# BlueToothStepperV2.net
KiCad netlist of a schematic drawn in EAGLE
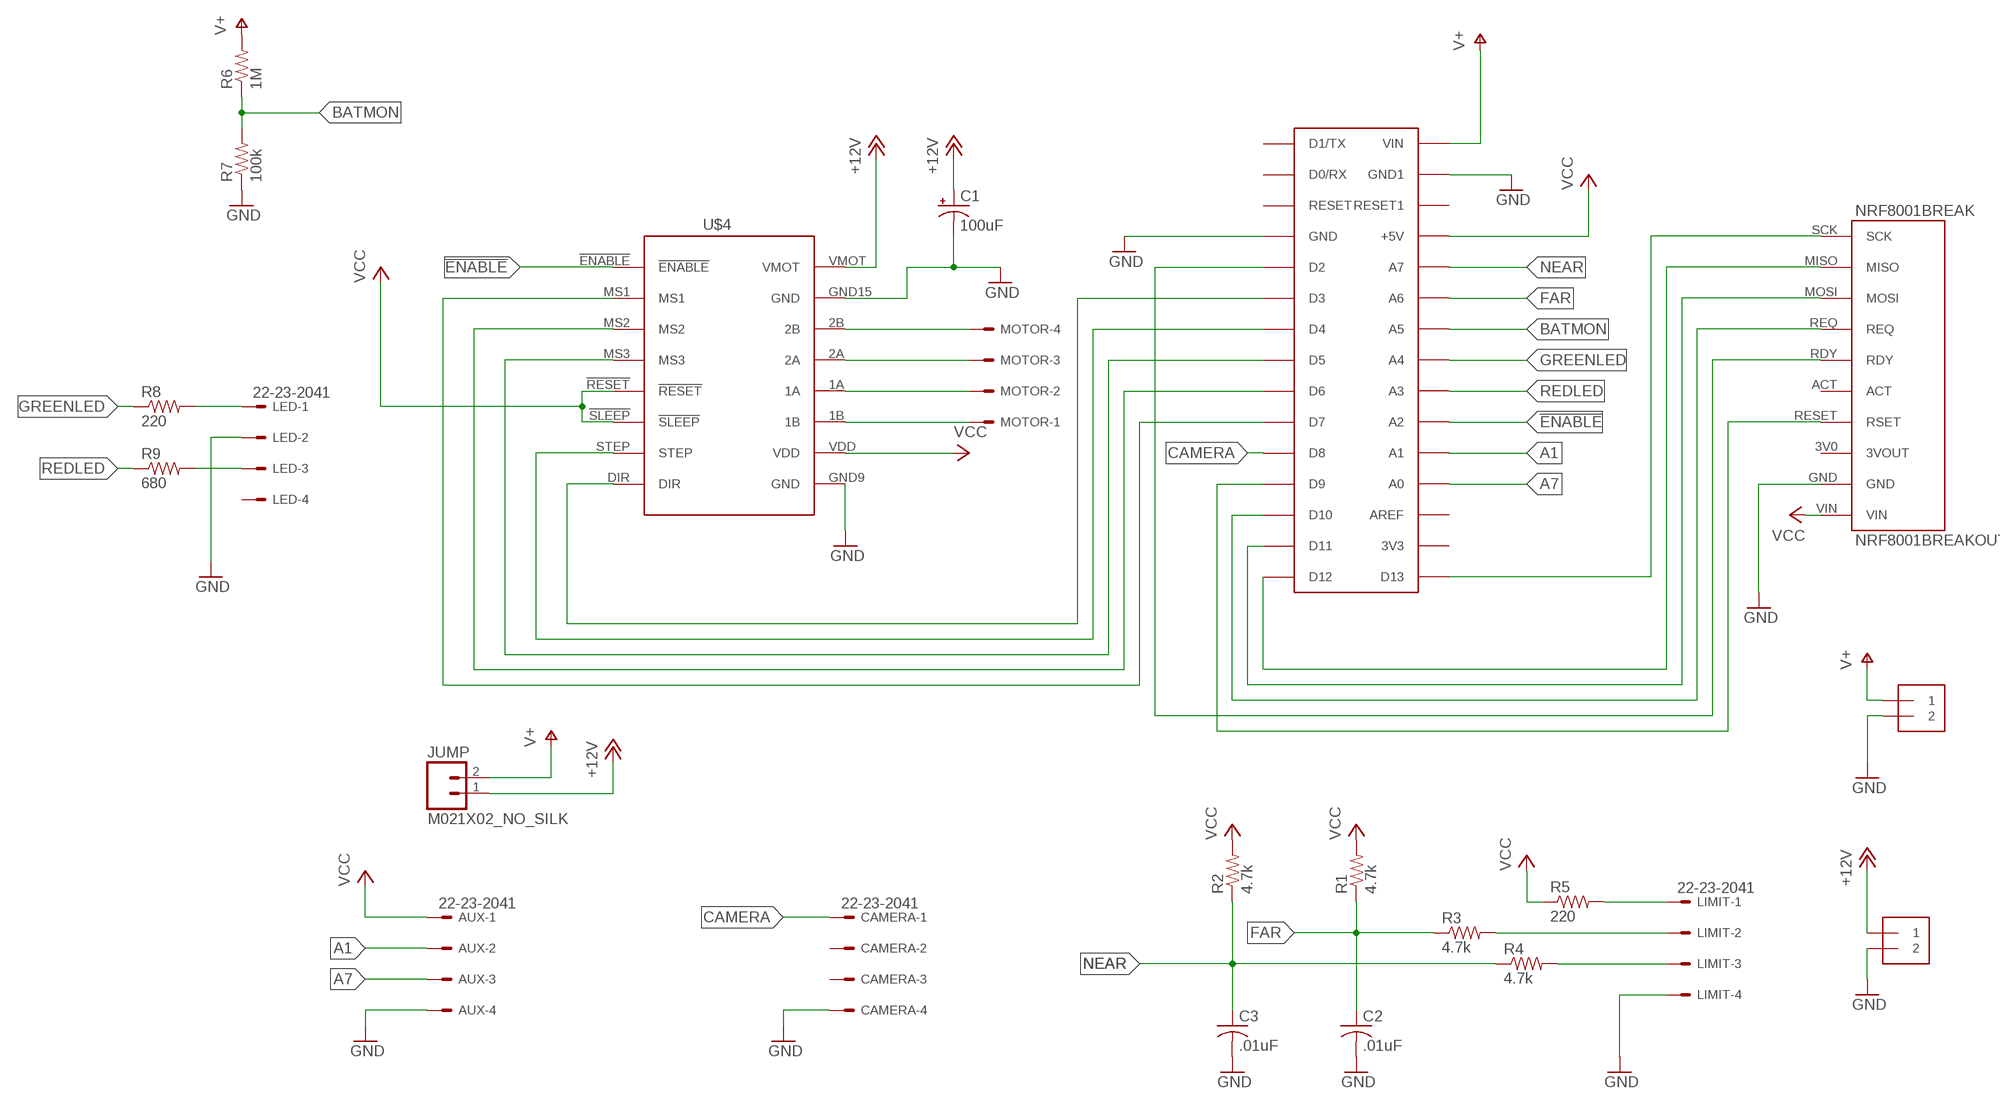
[diagram p0: schematic, sheet 1]

(export (version "E")
  (design (tool "Eeschema 10.0.6"))
  (components
    (comp (ref "7VOLT")
      (value "1X2-3.5MM")
      (footprint "eagle-import:1X2-3.5MM")
      (libsource (lib "eagle-import") (part "1X2-3.5MM"))
    )
    (comp (ref "12VOLT")
      (value "1X2-3.5MM")
      (footprint "eagle-import:1X2-3.5MM")
      (libsource (lib "eagle-import") (part "1X2-3.5MM"))
    )
    (comp (ref "AUX")
      (value "22-23-2041")
      (footprint "eagle-import:22-23-2041")
      (fields (field (name "MF") "MOLEX"))
      (libsource (lib "eagle-import") (part "22-23-2041"))
    )
    (comp (ref "C1")
      (value "100uF")
      (footprint "eagle-import:E3,5-8")
      (libsource (lib "eagle-import") (part "CPOL-USE3.5-8"))
    )
    (comp (ref "C2")
      (value ".01uF")
      (footprint "eagle-import:C050-030X075")
      (libsource (lib "eagle-import") (part "C-US050-030X075"))
    )
    (comp (ref "C3")
      (value ".01uF")
      (footprint "eagle-import:C050-030X075")
      (libsource (lib "eagle-import") (part "C-US050-030X075"))
    )
    (comp (ref "CAMERA")
      (value "22-23-2041")
      (footprint "eagle-import:22-23-2041")
      (fields (field (name "MF") "MOLEX"))
      (libsource (lib "eagle-import") (part "22-23-2041"))
    )
    (comp (ref "JUMP")
      (value "M021X02_NO_SILK")
      (footprint "eagle-import:1X02_NO_SILK")
      (libsource (lib "eagle-import") (part "M021X02_NO_SILK"))
    )
    (comp (ref "LED")
      (value "22-23-2041")
      (footprint "eagle-import:22-23-2041")
      (fields (field (name "MF") "MOLEX"))
      (libsource (lib "eagle-import") (part "22-23-2041"))
    )
    (comp (ref "LIMIT")
      (value "22-23-2041")
      (footprint "eagle-import:22-23-2041")
      (fields (field (name "MF") "MOLEX"))
      (libsource (lib "eagle-import") (part "22-23-2041"))
    )
    (comp (ref "MOTOR")
      (value "22-23-2041")
      (footprint "eagle-import:22-23-2041")
      (fields (field (name "MF") "MOLEX"))
      (libsource (lib "eagle-import") (part "22-23-2041"))
    )
    (comp (ref "NANO")
      (value "ARDUINONANO")
      (footprint "eagle-import:PDIP-32")
      (libsource (lib "eagle-import") (part "ARDUINONANO"))
    )
    (comp (ref "NRF8001BREAK")
      (value "NRF8001BREAKOUT")
      (footprint "eagle-import:BREAKOUTV2")
      (libsource (lib "eagle-import") (part "NRF8001BREAKOUT"))
    )
    (comp (ref "R1")
      (value "4.7k")
      (footprint "eagle-import:0207_9")
      (libsource (lib "eagle-import") (part "R-US_0207/9"))
    )
    (comp (ref "R2")
      (value "4.7k")
      (footprint "eagle-import:0207_9")
      (libsource (lib "eagle-import") (part "R-US_0207/9"))
    )
    (comp (ref "R3")
      (value "4.7k")
      (footprint "eagle-import:0207_9")
      (libsource (lib "eagle-import") (part "R-US_0207/9"))
    )
    (comp (ref "R4")
      (value "4.7k")
      (footprint "eagle-import:0207_9")
      (libsource (lib "eagle-import") (part "R-US_0207/9"))
    )
    (comp (ref "R5")
      (value "220")
      (footprint "eagle-import:0207_9")
      (libsource (lib "eagle-import") (part "R-US_0207/9"))
    )
    (comp (ref "R6")
      (value "1M")
      (footprint "eagle-import:0207_9")
      (libsource (lib "eagle-import") (part "R-US_0207/9"))
    )
    (comp (ref "R7")
      (value "100k")
      (footprint "eagle-import:0207_9")
      (libsource (lib "eagle-import") (part "R-US_0207/9"))
    )
    (comp (ref "R8")
      (value "220")
      (footprint "eagle-import:0207_9")
      (libsource (lib "eagle-import") (part "R-US_0207/9"))
    )
    (comp (ref "R9")
      (value "680")
      (footprint "eagle-import:0207_9")
      (libsource (lib "eagle-import") (part "R-US_0207/9"))
    )
    (comp (ref "U$4")
      (value "STEPPER1616PINV2")
      (footprint "eagle-import:STEPPER16PINV2")
      (libsource (lib "eagle-import") (part "STEPPER1616PINV2"))
    )
  )
  (nets
    (net (code "1") (name "+12V") (class "Default")
      (node (ref "12VOLT") (pin "1") (pinfunction "1_1") (pintype "passive"))
      (node (ref "C1") (pin "+") (pinfunction "+_+") (pintype "passive"))
      (node (ref "JUMP") (pin "1") (pinfunction "1_1") (pintype "passive"))
      (node (ref "U$4") (pin "VMOT") (pinfunction "VMOT_VMOT") (pintype "bidirectional"))
    )
    (net (code "2") (name "/~{ENABLE}") (class "Default")
      (node (ref "NANO") (pin "A2") (pinfunction "A2_A2") (pintype "bidirectional"))
      (node (ref "U$4") (pin "!ENABLE") (pinfunction "~{ENABLE}_!ENABLE") (pintype "bidirectional"))
    )
    (net (code "3") (name "A1") (class "Default")
      (node (ref "AUX") (pin "2") (pinfunction "S_2") (pintype "passive"))
      (node (ref "NANO") (pin "A1") (pinfunction "A1_A1") (pintype "bidirectional"))
    )
    (net (code "4") (name "A7") (class "Default")
      (node (ref "AUX") (pin "3") (pinfunction "S_3") (pintype "passive"))
      (node (ref "NANO") (pin "A0") (pinfunction "A0_A0") (pintype "bidirectional"))
    )
    (net (code "5") (name "BATMON") (class "Default")
      (node (ref "NANO") (pin "A5") (pinfunction "A5_A5") (pintype "bidirectional"))
      (node (ref "R6") (pin "1") (pinfunction "1_1") (pintype "passive"))
      (node (ref "R7") (pin "2") (pinfunction "2_2") (pintype "passive"))
    )
    (net (code "6") (name "CAMERA") (class "Default")
      (node (ref "CAMERA") (pin "1") (pinfunction "S_1") (pintype "passive"))
      (node (ref "NANO") (pin "D8") (pinfunction "D8_D8") (pintype "bidirectional"))
    )
    (net (code "7") (name "FAR") (class "Default")
      (node (ref "C2") (pin "1") (pinfunction "1_1") (pintype "passive"))
      (node (ref "NANO") (pin "A6") (pinfunction "A6_A6") (pintype "bidirectional"))
      (node (ref "R1") (pin "1") (pinfunction "1_1") (pintype "passive"))
      (node (ref "R3") (pin "1") (pinfunction "1_1") (pintype "passive"))
    )
    (net (code "8") (name "GND") (class "Default")
      (node (ref "12VOLT") (pin "2") (pinfunction "2_2") (pintype "passive"))
      (node (ref "7VOLT") (pin "2") (pinfunction "2_2") (pintype "passive"))
      (node (ref "AUX") (pin "4") (pinfunction "S_4") (pintype "passive"))
      (node (ref "C1") (pin "-") (pinfunction "-_-") (pintype "passive"))
      (node (ref "C2") (pin "2") (pinfunction "2_2") (pintype "passive"))
      (node (ref "C3") (pin "2") (pinfunction "2_2") (pintype "passive"))
      (node (ref "CAMERA") (pin "4") (pinfunction "S_4") (pintype "passive"))
      (node (ref "LED") (pin "2") (pinfunction "S_2") (pintype "passive"))
      (node (ref "LIMIT") (pin "4") (pinfunction "S_4") (pintype "passive"))
      (node (ref "NANO") (pin "GND") (pinfunction "GND_GND") (pintype "bidirectional"))
      (node (ref "NANO") (pin "GND1") (pinfunction "GND1_GND1") (pintype "bidirectional"))
      (node (ref "NRF8001BREAK") (pin "GND") (pinfunction "GND_GND") (pintype "bidirectional"))
      (node (ref "R7") (pin "1") (pinfunction "1_1") (pintype "passive"))
      (node (ref "U$4") (pin "GND15") (pinfunction "GND_GND15") (pintype "bidirectional"))
      (node (ref "U$4") (pin "GND9") (pinfunction "GND_GND9") (pintype "bidirectional"))
    )
    (net (code "9") (name "GREENLED") (class "Default")
      (node (ref "NANO") (pin "A4") (pinfunction "A4_A4") (pintype "bidirectional"))
      (node (ref "R8") (pin "1") (pinfunction "1_1") (pintype "passive"))
    )
    (net (code "10") (name "NEAR") (class "Default")
      (node (ref "C3") (pin "1") (pinfunction "1_1") (pintype "passive"))
      (node (ref "NANO") (pin "A7") (pinfunction "A7_A7") (pintype "bidirectional"))
      (node (ref "R2") (pin "1") (pinfunction "1_1") (pintype "passive"))
      (node (ref "R4") (pin "1") (pinfunction "1_1") (pintype "passive"))
    )
    (net (code "11") (name "Net-(LEDA-S)") (class "Default")
      (node (ref "LED") (pin "1") (pinfunction "S_1") (pintype "passive"))
      (node (ref "R8") (pin "2") (pinfunction "2_2") (pintype "passive"))
    )
    (net (code "12") (name "Net-(LEDC-S)") (class "Default")
      (node (ref "LED") (pin "3") (pinfunction "S_3") (pintype "passive"))
      (node (ref "R9") (pin "2") (pinfunction "2_2") (pintype "passive"))
    )
    (net (code "13") (name "Net-(LIMITA-S)") (class "Default")
      (node (ref "LIMIT") (pin "1") (pinfunction "S_1") (pintype "passive"))
      (node (ref "R5") (pin "2") (pinfunction "2_2") (pintype "passive"))
    )
    (net (code "14") (name "Net-(LIMITB-S)") (class "Default")
      (node (ref "LIMIT") (pin "2") (pinfunction "S_2") (pintype "passive"))
      (node (ref "R3") (pin "2") (pinfunction "2_2") (pintype "passive"))
    )
    (net (code "15") (name "Net-(LIMITC-S)") (class "Default")
      (node (ref "LIMIT") (pin "3") (pinfunction "S_3") (pintype "passive"))
      (node (ref "R4") (pin "2") (pinfunction "2_2") (pintype "passive"))
    )
    (net (code "16") (name "Net-(MOTORA-S)") (class "Default")
      (node (ref "MOTOR") (pin "1") (pinfunction "S_1") (pintype "passive"))
      (node (ref "U$4") (pin "1B") (pinfunction "1B_1B") (pintype "bidirectional"))
    )
    (net (code "17") (name "Net-(MOTORB-S)") (class "Default")
      (node (ref "MOTOR") (pin "2") (pinfunction "S_2") (pintype "passive"))
      (node (ref "U$4") (pin "1A") (pinfunction "1A_1A") (pintype "bidirectional"))
    )
    (net (code "18") (name "Net-(MOTORC-S)") (class "Default")
      (node (ref "MOTOR") (pin "3") (pinfunction "S_3") (pintype "passive"))
      (node (ref "U$4") (pin "2A") (pinfunction "2A_2A") (pintype "bidirectional"))
    )
    (net (code "19") (name "Net-(MOTORD-S)") (class "Default")
      (node (ref "MOTOR") (pin "4") (pinfunction "S_4") (pintype "passive"))
      (node (ref "U$4") (pin "2B") (pinfunction "2B_2B") (pintype "bidirectional"))
    )
    (net (code "20") (name "Net-(NANO-PadD2)") (class "Default")
      (node (ref "NANO") (pin "D2") (pinfunction "D2_D2") (pintype "bidirectional"))
      (node (ref "NRF8001BREAK") (pin "RDY") (pinfunction "RDY_RDY") (pintype "bidirectional"))
    )
    (net (code "21") (name "Net-(NANO-PadD3)") (class "Default")
      (node (ref "NANO") (pin "D3") (pinfunction "D3_D3") (pintype "bidirectional"))
      (node (ref "U$4") (pin "DIR") (pinfunction "DIR_DIR") (pintype "bidirectional"))
    )
    (net (code "22") (name "Net-(NANO-PadD4)") (class "Default")
      (node (ref "NANO") (pin "D4") (pinfunction "D4_D4") (pintype "bidirectional"))
      (node (ref "U$4") (pin "STEP") (pinfunction "STEP_STEP") (pintype "bidirectional"))
    )
    (net (code "23") (name "Net-(NANO-PadD5)") (class "Default")
      (node (ref "NANO") (pin "D5") (pinfunction "D5_D5") (pintype "bidirectional"))
      (node (ref "U$4") (pin "MS3") (pinfunction "MS3_MS3") (pintype "bidirectional"))
    )
    (net (code "24") (name "Net-(NANO-PadD6)") (class "Default")
      (node (ref "NANO") (pin "D6") (pinfunction "D6_D6") (pintype "bidirectional"))
      (node (ref "U$4") (pin "MS2") (pinfunction "MS2_MS2") (pintype "bidirectional"))
    )
    (net (code "25") (name "Net-(NANO-PadD7)") (class "Default")
      (node (ref "NANO") (pin "D7") (pinfunction "D7_D7") (pintype "bidirectional"))
      (node (ref "U$4") (pin "MS1") (pinfunction "MS1_MS1") (pintype "bidirectional"))
    )
    (net (code "26") (name "Net-(NANO-PadD10)") (class "Default")
      (node (ref "NANO") (pin "D10") (pinfunction "D10_D10") (pintype "bidirectional"))
      (node (ref "NRF8001BREAK") (pin "REQ") (pinfunction "REQ_REQ") (pintype "bidirectional"))
    )
    (net (code "27") (name "Net-(NANO-PadD11)") (class "Default")
      (node (ref "NANO") (pin "D11") (pinfunction "D11_D11") (pintype "bidirectional"))
      (node (ref "NRF8001BREAK") (pin "MOSI") (pinfunction "MOSI_MOSI") (pintype "bidirectional"))
    )
    (net (code "28") (name "Net-(NANO-PadD12)") (class "Default")
      (node (ref "NANO") (pin "D12") (pinfunction "D12_D12") (pintype "bidirectional"))
      (node (ref "NRF8001BREAK") (pin "MISO") (pinfunction "MISO_MISO") (pintype "bidirectional"))
    )
    (net (code "29") (name "Net-(NANO-PadD13)") (class "Default")
      (node (ref "NANO") (pin "D13") (pinfunction "D13_D13") (pintype "bidirectional"))
      (node (ref "NRF8001BREAK") (pin "SCK") (pinfunction "SCK_SCK") (pintype "bidirectional"))
    )
    (net (code "30") (name "Net-(NRF8001BREAK-RSET)") (class "Default")
      (node (ref "NANO") (pin "D9") (pinfunction "D9_D9") (pintype "bidirectional"))
      (node (ref "NRF8001BREAK") (pin "RESET") (pinfunction "RSET_RESET") (pintype "bidirectional"))
    )
    (net (code "31") (name "REDLED") (class "Default")
      (node (ref "NANO") (pin "A3") (pinfunction "A3_A3") (pintype "bidirectional"))
      (node (ref "R9") (pin "1") (pinfunction "1_1") (pintype "passive"))
    )
    (net (code "32") (name "V+") (class "Default")
      (node (ref "7VOLT") (pin "1") (pinfunction "1_1") (pintype "passive"))
      (node (ref "JUMP") (pin "2") (pinfunction "2_2") (pintype "passive"))
      (node (ref "NANO") (pin "VIN") (pinfunction "VIN_VIN") (pintype "bidirectional"))
      (node (ref "R6") (pin "2") (pinfunction "2_2") (pintype "passive"))
    )
    (net (code "33") (name "VCC") (class "Default")
      (node (ref "AUX") (pin "1") (pinfunction "S_1") (pintype "passive"))
      (node (ref "NANO") (pin "+5V") (pinfunction "+5V_+5V") (pintype "bidirectional"))
      (node (ref "NRF8001BREAK") (pin "VIN") (pinfunction "VIN_VIN") (pintype "bidirectional"))
      (node (ref "R1") (pin "2") (pinfunction "2_2") (pintype "passive"))
      (node (ref "R2") (pin "2") (pinfunction "2_2") (pintype "passive"))
      (node (ref "R5") (pin "1") (pinfunction "1_1") (pintype "passive"))
      (node (ref "U$4") (pin "!RESET") (pinfunction "~{RESET}_!RESET") (pintype "bidirectional"))
      (node (ref "U$4") (pin "!SLEEP") (pinfunction "~{SLEEP}_!SLEEP") (pintype "bidirectional"))
      (node (ref "U$4") (pin "VDD") (pinfunction "VDD_VDD") (pintype "bidirectional"))
    )
    (net (code "34") (name "unconnected-(CAMERAB-S-Pad2)") (class "Default")
      (node (ref "CAMERA") (pin "2") (pinfunction "S_2") (pintype "passive"))
    )
    (net (code "35") (name "unconnected-(CAMERAC-S-Pad3)") (class "Default")
      (node (ref "CAMERA") (pin "3") (pinfunction "S_3") (pintype "passive"))
    )
    (net (code "36") (name "unconnected-(LEDD-S-Pad4)") (class "Default")
      (node (ref "LED") (pin "4") (pinfunction "S_4") (pintype "passive"))
    )
    (net (code "37") (name "unconnected-(NANO-Pad3V3)") (class "Default")
      (node (ref "NANO") (pin "3V3") (pinfunction "3V3_3V3") (pintype "bidirectional"))
    )
    (net (code "38") (name "unconnected-(NANO-PadAREF)") (class "Default")
      (node (ref "NANO") (pin "AREF") (pinfunction "AREF_AREF") (pintype "bidirectional"))
    )
    (net (code "39") (name "unconnected-(NANO-PadD0{slash}RX)") (class "Default")
      (node (ref "NANO") (pin "D0/RX") (pinfunction "D0/RX_D0/RX") (pintype "bidirectional"))
    )
    (net (code "40") (name "unconnected-(NANO-PadD1{slash}TX)") (class "Default")
      (node (ref "NANO") (pin "D1/TX") (pinfunction "D1/TX_D1/TX") (pintype "bidirectional"))
    )
    (net (code "41") (name "unconnected-(NANO-PadRESET)") (class "Default")
      (node (ref "NANO") (pin "RESET") (pinfunction "RESET_RESET") (pintype "bidirectional"))
    )
    (net (code "42") (name "unconnected-(NANO-PadRESET1)") (class "Default")
      (node (ref "NANO") (pin "RESET1") (pinfunction "RESET1_RESET1") (pintype "bidirectional"))
    )
    (net (code "43") (name "unconnected-(NRF8001BREAK-3VOUT-Pad3V0)") (class "Default")
      (node (ref "NRF8001BREAK") (pin "3V0") (pinfunction "3VOUT_3V0") (pintype "bidirectional"))
    )
    (net (code "44") (name "unconnected-(NRF8001BREAK-PadACT)") (class "Default")
      (node (ref "NRF8001BREAK") (pin "ACT") (pinfunction "ACT_ACT") (pintype "bidirectional"))
    )
  )
)
